# BPC_PWR_TOP.net
KiCad netlist of a schematic drawn in Altium Designer
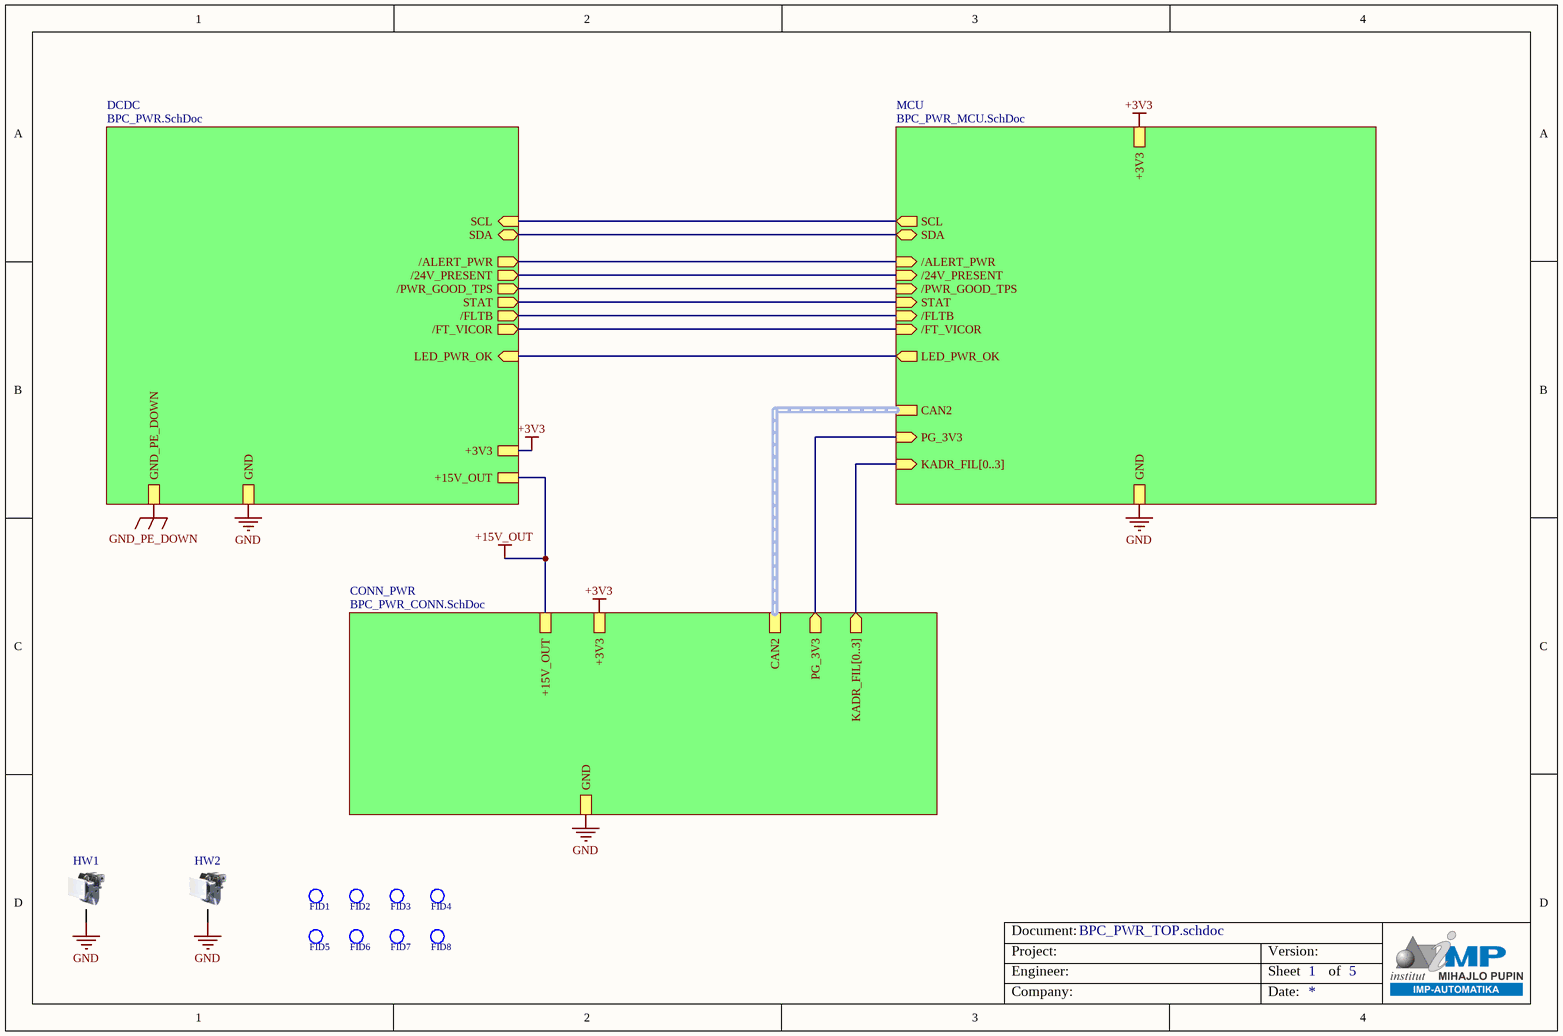
[diagram p0: BPC_PWR_TOP.schdoc]

(export (version "E")
  (design (tool "Eeschema 10.0.6"))
  (components
    (comp (ref "FID1")
      (value "Fiducial Mark Round 1.6mm")
      (footprint "FIDUCIAL_3.2_1.6")
      (libsource (lib "MS IMP Library") (part "Fiducial 1.6mm Round MS"))
    )
    (comp (ref "FID2")
      (value "Fiducial Mark Round 1.6mm")
      (footprint "FIDUCIAL_3.2_1.6")
      (libsource (lib "MS IMP Library") (part "Fiducial 1.6mm Round MS"))
    )
    (comp (ref "FID3")
      (value "Fiducial Mark Round 1.6mm")
      (footprint "FIDUCIAL_3.2_1.6")
      (libsource (lib "MS IMP Library") (part "Fiducial 1.6mm Round MS"))
    )
    (comp (ref "FID4")
      (value "Fiducial Mark Round 1.6mm")
      (footprint "FIDUCIAL_3.2_1.6")
      (libsource (lib "MS IMP Library") (part "Fiducial 1.6mm Round MS"))
    )
    (comp (ref "FID5")
      (value "Fiducial Mark Round 1.6mm")
      (footprint "FIDUCIAL_3.2_1.6")
      (libsource (lib "MS IMP Library") (part "Fiducial 1.6mm Round MS"))
    )
    (comp (ref "FID6")
      (value "Fiducial Mark Round 1.6mm")
      (footprint "FIDUCIAL_3.2_1.6")
      (libsource (lib "MS IMP Library") (part "Fiducial 1.6mm Round MS"))
    )
    (comp (ref "FID7")
      (value "Fiducial Mark Round 1.6mm")
      (footprint "FIDUCIAL_3.2_1.6")
      (libsource (lib "MS IMP Library") (part "Fiducial 1.6mm Round MS"))
    )
    (comp (ref "FID8")
      (value "Fiducial Mark Round 1.6mm")
      (footprint "FIDUCIAL_3.2_1.6")
      (libsource (lib "MS IMP Library") (part "Fiducial 1.6mm Round MS"))
    )
    (comp (ref "HW1")
      (value "Extractor Handle")
      (footprint "Extractor Handle 3685.587 - Lower MS")
      (description "HW Extractor Handle Type I 15mm 3685.587")
      (fields
        (field (name "DISTRIBUTOR PART NUMBER") "345-1342-ND")
        (field (name "MANUFACTURER") "Wakefield-Vette")
      )
      (libsource (lib "MS IMP Library") (part "HW Extractor Handle Type I 15mm 3685.587"))
    )
    (comp (ref "HW2")
      (value "Extractor Handle")
      (footprint "Extractor Handle 3685.587 - Upper MS")
      (description "HW Extractor Handle Type I 15mm 3685.587")
      (fields
        (field (name "DISTRIBUTOR PART NUMBER") "345-1342-ND")
        (field (name "MANUFACTURER") "Wakefield-Vette")
      )
      (libsource (lib "MS IMP Library") (part "HW Extractor Handle Type I 15mm 3685.587"))
    )
  )
  (nets
    (net (code "15") (name "GND") (class "Default")
      (node (ref "HW1") (pin "0") (pinfunction "0_0") (pintype "passive"))
      (node (ref "HW2") (pin "0") (pinfunction "0_0") (pintype "passive"))
    )
  )
)
